# Main.net
KiCad netlist of a schematic drawn in Altium Designer
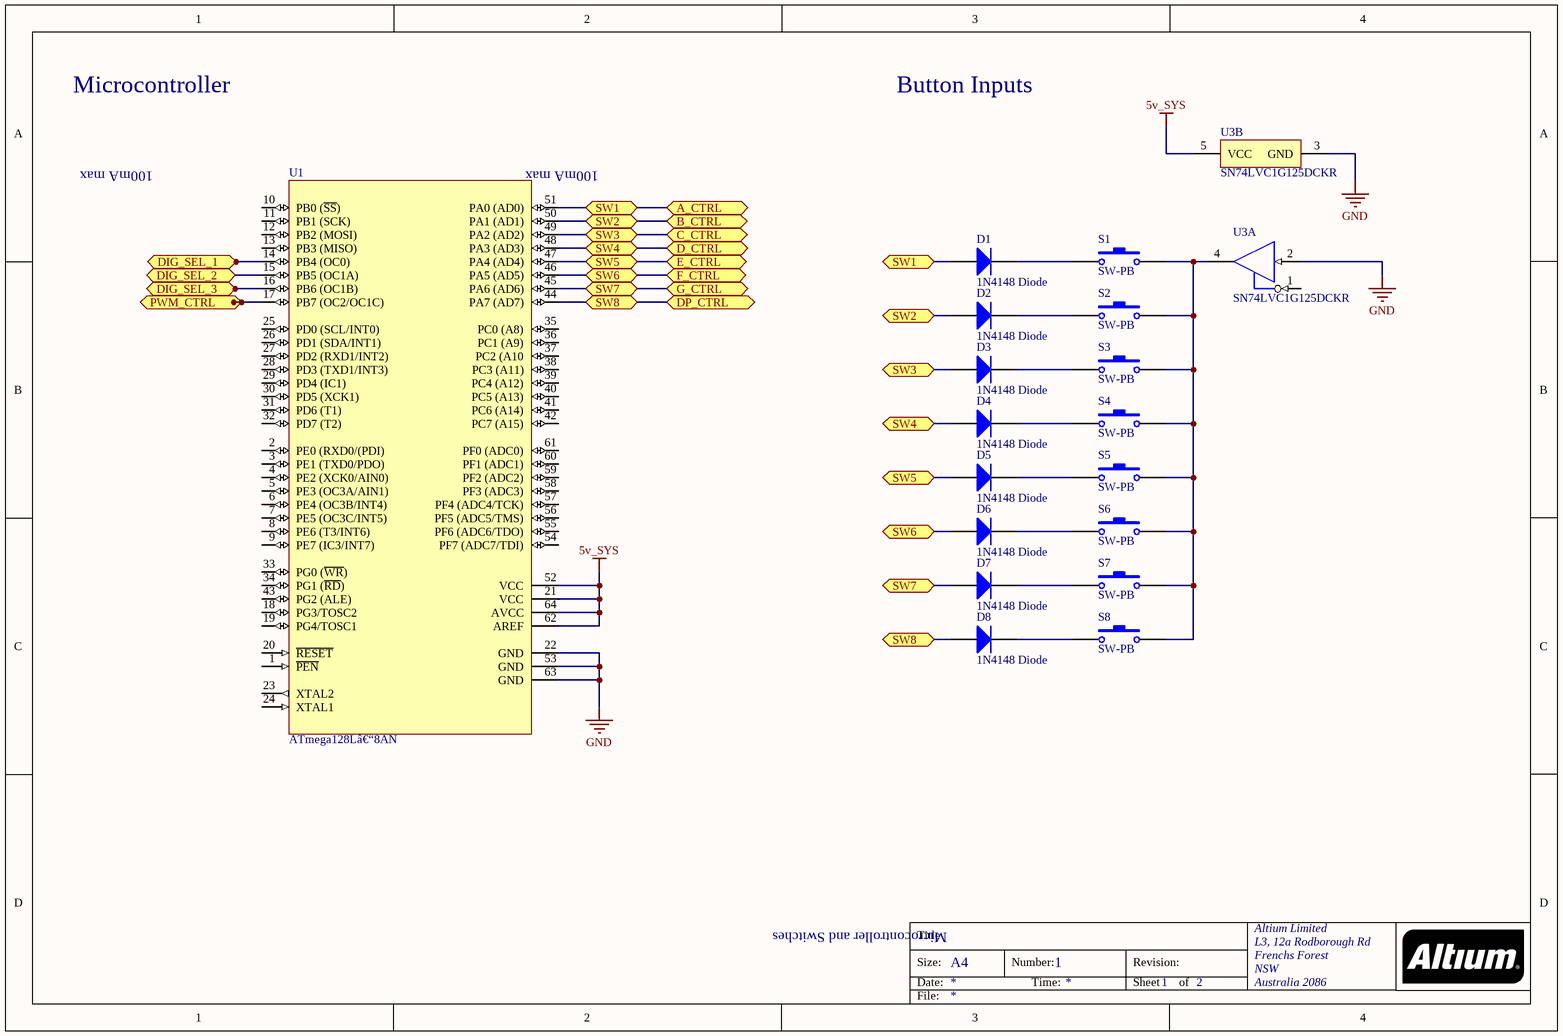
[diagram p0: Main.SchDoc]

(export (version "E")
  (design (tool "Eeschema 10.0.6"))
  (components
    (comp (ref "D1")
      (value "1N4148 Diode")
      (footprint "S01575 Diode")
      (description "Diode")
      (libsource (lib "lab2") (part "Diode"))
    )
    (comp (ref "D2")
      (value "1N4148 Diode")
      (footprint "S01575 Diode")
      (description "Diode")
      (libsource (lib "lab2") (part "Diode"))
    )
    (comp (ref "D3")
      (value "1N4148 Diode")
      (footprint "S01575 Diode")
      (description "Diode")
      (libsource (lib "lab2") (part "Diode"))
    )
    (comp (ref "D4")
      (value "1N4148 Diode")
      (footprint "S01575 Diode")
      (description "Diode")
      (libsource (lib "lab2") (part "Diode"))
    )
    (comp (ref "D5")
      (value "1N4148 Diode")
      (footprint "S01575 Diode")
      (description "Diode")
      (libsource (lib "lab2") (part "Diode"))
    )
    (comp (ref "D6")
      (value "1N4148 Diode")
      (footprint "S01575 Diode")
      (description "Diode")
      (libsource (lib "lab2") (part "Diode"))
    )
    (comp (ref "D7")
      (value "1N4148 Diode")
      (footprint "S01575 Diode")
      (description "Diode")
      (libsource (lib "lab2") (part "Diode"))
    )
    (comp (ref "D8")
      (value "1N4148 Diode")
      (footprint "S01575 Diode")
      (description "Diode")
      (libsource (lib "lab2") (part "Diode"))
    )
    (comp (ref "S1")
      (value "SW-PB")
      (footprint "SW-PB")
      (description "Switch")
      (libsource (lib "lab2") (part "SW-PB"))
    )
    (comp (ref "S2")
      (value "SW-PB")
      (footprint "SW-PB")
      (description "Switch")
      (libsource (lib "lab2") (part "SW-PB"))
    )
    (comp (ref "S3")
      (value "SW-PB")
      (footprint "SW-PB")
      (description "Switch")
      (libsource (lib "lab2") (part "SW-PB"))
    )
    (comp (ref "S4")
      (value "SW-PB")
      (footprint "SW-PB")
      (description "Switch")
      (libsource (lib "lab2") (part "SW-PB"))
    )
    (comp (ref "S5")
      (value "SW-PB")
      (footprint "SW-PB")
      (description "Switch")
      (libsource (lib "lab2") (part "SW-PB"))
    )
    (comp (ref "S6")
      (value "SW-PB")
      (footprint "SW-PB")
      (description "Switch")
      (libsource (lib "lab2") (part "SW-PB"))
    )
    (comp (ref "S7")
      (value "SW-PB")
      (footprint "SW-PB")
      (description "Switch")
      (libsource (lib "lab2") (part "SW-PB"))
    )
    (comp (ref "S8")
      (value "SW-PB")
      (footprint "SW-PB")
      (description "Switch")
      (libsource (lib "lab2") (part "SW-PB"))
    )
    (comp (ref "U1")
      (value "ATmega128Lâ€“8AN")
      (footprint "64A_L")
      (libsource (lib "Altium Content Vault") (part "MC-8B-AT64-SQ64"))
    )
    (comp (ref "U3")
      (value "SN74LVC1G125DCKR")
      (footprint "DCK0005A_N")
      (description "Single Bus Buffer Gate With 3-State Outputs, DCK0005A, LARGE T&R")
      (fields
        (field (name "GENERIC PART NUMBER") "SN74LVC1G125")
        (field (name "MANUFACTURER") "Texas Instruments")
      )
      (libsource (lib "") (part "TI-SN74AXXXX1X125-5_1"))
    )
  )
  (nets
    (net (code "1") (name "/A_CTRL") (class "Default")
      (node (ref "D1") (pin "3") (pinfunction "A_3") (pintype "passive"))
      (node (ref "U1") (pin "51") (pinfunction "PA0_(AD0)_51") (pintype "bidirectional"))
    )
    (net (code "2") (name "/B_CTRL") (class "Default")
      (node (ref "D2") (pin "3") (pinfunction "A_3") (pintype "passive"))
      (node (ref "U1") (pin "50") (pinfunction "PA1_(AD1)_50") (pintype "bidirectional"))
    )
    (net (code "3") (name "/C_CTRL") (class "Default")
      (node (ref "D3") (pin "3") (pinfunction "A_3") (pintype "passive"))
      (node (ref "U1") (pin "49") (pinfunction "PA2_(AD2)_49") (pintype "bidirectional"))
    )
    (net (code "4") (name "/DIG_SEL_1") (class "Default")
      (node (ref "U1") (pin "14") (pinfunction "PB4_(OC0)_14") (pintype "bidirectional"))
    )
    (net (code "5") (name "/DIG_SEL_2") (class "Default")
      (node (ref "U1") (pin "15") (pinfunction "PB5_(OC1A)_15") (pintype "bidirectional"))
    )
    (net (code "6") (name "/DIG_SEL_3") (class "Default")
      (node (ref "U1") (pin "16") (pinfunction "PB6_(OC1B)_16") (pintype "bidirectional"))
    )
    (net (code "7") (name "/DP_CTRL") (class "Default")
      (node (ref "D8") (pin "3") (pinfunction "A_3") (pintype "passive"))
      (node (ref "U1") (pin "44") (pinfunction "PA7_(AD7)_44") (pintype "bidirectional"))
    )
    (net (code "8") (name "/D_CTRL") (class "Default")
      (node (ref "D4") (pin "3") (pinfunction "A_3") (pintype "passive"))
      (node (ref "U1") (pin "48") (pinfunction "PA3_(AD3)_48") (pintype "bidirectional"))
    )
    (net (code "9") (name "/E_CTRL") (class "Default")
      (node (ref "D5") (pin "3") (pinfunction "A_3") (pintype "passive"))
      (node (ref "U1") (pin "47") (pinfunction "PA4_(AD4)_47") (pintype "bidirectional"))
    )
    (net (code "10") (name "/F_CTRL") (class "Default")
      (node (ref "D6") (pin "3") (pinfunction "A_3") (pintype "passive"))
      (node (ref "U1") (pin "46") (pinfunction "PA5_(AD5)_46") (pintype "bidirectional"))
    )
    (net (code "11") (name "/G_CTRL") (class "Default")
      (node (ref "D7") (pin "3") (pinfunction "A_3") (pintype "passive"))
      (node (ref "U1") (pin "45") (pinfunction "PA6_(AD6)_45") (pintype "bidirectional"))
    )
    (net (code "12") (name "/PWM_CTRL") (class "Default")
      (node (ref "U1") (pin "17") (pinfunction "PB7_(OC2/OC1C)_17") (pintype "bidirectional"))
    )
    (net (code "13") (name "5v_SYS") (class "Default")
      (node (ref "U1") (pin "21") (pinfunction "VCC_21") (pintype "power_in"))
      (node (ref "U1") (pin "52") (pinfunction "VCC_52") (pintype "power_in"))
      (node (ref "U1") (pin "62") (pinfunction "AREF_62") (pintype "passive"))
      (node (ref "U1") (pin "64") (pinfunction "AVCC_64") (pintype "power_in"))
      (node (ref "U3") (pin "5") (pinfunction "VCC_5") (pintype "power_in"))
    )
    (net (code "14") (name "GND") (class "Default")
      (node (ref "U1") (pin "22") (pinfunction "GND_22") (pintype "power_in"))
      (node (ref "U1") (pin "53") (pinfunction "GND_53") (pintype "power_in"))
      (node (ref "U1") (pin "63") (pinfunction "GND_63") (pintype "power_in"))
      (node (ref "U3") (pin "2") (pinfunction "A_2") (pintype "input"))
      (node (ref "U3") (pin "3") (pinfunction "GND_3") (pintype "power_in"))
    )
    (net (code "15") (name "Net-(D1-K)") (class "Default")
      (node (ref "D1") (pin "1") (pinfunction "K_1") (pintype "passive"))
      (node (ref "S1") (pin "1") (pinfunction "1_1") (pintype "passive"))
    )
    (net (code "16") (name "Net-(D2-K)") (class "Default")
      (node (ref "D2") (pin "1") (pinfunction "K_1") (pintype "passive"))
      (node (ref "S2") (pin "1") (pinfunction "1_1") (pintype "passive"))
    )
    (net (code "17") (name "Net-(D3-K)") (class "Default")
      (node (ref "D3") (pin "1") (pinfunction "K_1") (pintype "passive"))
      (node (ref "S3") (pin "1") (pinfunction "1_1") (pintype "passive"))
    )
    (net (code "18") (name "Net-(D4-K)") (class "Default")
      (node (ref "D4") (pin "1") (pinfunction "K_1") (pintype "passive"))
      (node (ref "S4") (pin "1") (pinfunction "1_1") (pintype "passive"))
    )
    (net (code "19") (name "Net-(D5-K)") (class "Default")
      (node (ref "D5") (pin "1") (pinfunction "K_1") (pintype "passive"))
      (node (ref "S5") (pin "1") (pinfunction "1_1") (pintype "passive"))
    )
    (net (code "20") (name "Net-(D6-K)") (class "Default")
      (node (ref "D6") (pin "1") (pinfunction "K_1") (pintype "passive"))
      (node (ref "S6") (pin "1") (pinfunction "1_1") (pintype "passive"))
    )
    (net (code "21") (name "Net-(D7-K)") (class "Default")
      (node (ref "D7") (pin "1") (pinfunction "K_1") (pintype "passive"))
      (node (ref "S7") (pin "1") (pinfunction "1_1") (pintype "passive"))
    )
    (net (code "22") (name "Net-(D8-K)") (class "Default")
      (node (ref "D8") (pin "1") (pinfunction "K_1") (pintype "passive"))
      (node (ref "S8") (pin "1") (pinfunction "1_1") (pintype "passive"))
    )
    (net (code "23") (name "Net-(U3A-Y)") (class "Default")
      (node (ref "S1") (pin "2") (pinfunction "2_2") (pintype "passive"))
      (node (ref "S2") (pin "2") (pinfunction "2_2") (pintype "passive"))
      (node (ref "S3") (pin "2") (pinfunction "2_2") (pintype "passive"))
      (node (ref "S4") (pin "2") (pinfunction "2_2") (pintype "passive"))
      (node (ref "S5") (pin "2") (pinfunction "2_2") (pintype "passive"))
      (node (ref "S6") (pin "2") (pinfunction "2_2") (pintype "passive"))
      (node (ref "S7") (pin "2") (pinfunction "2_2") (pintype "passive"))
      (node (ref "S8") (pin "2") (pinfunction "2_2") (pintype "passive"))
      (node (ref "U3") (pin "4") (pinfunction "Y_4") (pintype "tri_state"))
    )
    (net (code "24") (name "unconnected-(U1-PB0_(~{SS})-Pad10)") (class "Default")
      (node (ref "U1") (pin "10") (pinfunction "PB0_(~{SS})_10") (pintype "bidirectional"))
    )
    (net (code "25") (name "unconnected-(U1-PB1_(SCK)-Pad11)") (class "Default")
      (node (ref "U1") (pin "11") (pinfunction "PB1_(SCK)_11") (pintype "bidirectional"))
    )
    (net (code "26") (name "unconnected-(U1-PB2_(MOSI)-Pad12)") (class "Default")
      (node (ref "U1") (pin "12") (pinfunction "PB2_(MOSI)_12") (pintype "bidirectional"))
    )
    (net (code "27") (name "unconnected-(U1-PB3_(MISO)-Pad13)") (class "Default")
      (node (ref "U1") (pin "13") (pinfunction "PB3_(MISO)_13") (pintype "bidirectional"))
    )
    (net (code "28") (name "unconnected-(U1-PC0_(A8)-Pad35)") (class "Default")
      (node (ref "U1") (pin "35") (pinfunction "PC0_(A8)_35") (pintype "bidirectional"))
    )
    (net (code "29") (name "unconnected-(U1-PC1_(A9)-Pad36)") (class "Default")
      (node (ref "U1") (pin "36") (pinfunction "PC1_(A9)_36") (pintype "bidirectional"))
    )
    (net (code "30") (name "unconnected-(U1-PC2_(A10-Pad37)") (class "Default")
      (node (ref "U1") (pin "37") (pinfunction "PC2_(A10_37") (pintype "bidirectional"))
    )
    (net (code "31") (name "unconnected-(U1-PC3_(A11)-Pad38)") (class "Default")
      (node (ref "U1") (pin "38") (pinfunction "PC3_(A11)_38") (pintype "bidirectional"))
    )
    (net (code "32") (name "unconnected-(U1-PC4_(A12)-Pad39)") (class "Default")
      (node (ref "U1") (pin "39") (pinfunction "PC4_(A12)_39") (pintype "bidirectional"))
    )
    (net (code "33") (name "unconnected-(U1-PC5_(A13)-Pad40)") (class "Default")
      (node (ref "U1") (pin "40") (pinfunction "PC5_(A13)_40") (pintype "bidirectional"))
    )
    (net (code "34") (name "unconnected-(U1-PC6_(A14)-Pad41)") (class "Default")
      (node (ref "U1") (pin "41") (pinfunction "PC6_(A14)_41") (pintype "bidirectional"))
    )
    (net (code "35") (name "unconnected-(U1-PC7_(A15)-Pad42)") (class "Default")
      (node (ref "U1") (pin "42") (pinfunction "PC7_(A15)_42") (pintype "bidirectional"))
    )
    (net (code "36") (name "unconnected-(U1-PD0_(SCL{slash}INT0)-Pad25)") (class "Default")
      (node (ref "U1") (pin "25") (pinfunction "PD0_(SCL/INT0)_25") (pintype "bidirectional"))
    )
    (net (code "37") (name "unconnected-(U1-PD1_(SDA{slash}INT1)-Pad26)") (class "Default")
      (node (ref "U1") (pin "26") (pinfunction "PD1_(SDA/INT1)_26") (pintype "bidirectional"))
    )
    (net (code "38") (name "unconnected-(U1-PD2_(RXD1{slash}INT2)-Pad27)") (class "Default")
      (node (ref "U1") (pin "27") (pinfunction "PD2_(RXD1/INT2)_27") (pintype "bidirectional"))
    )
    (net (code "39") (name "unconnected-(U1-PD3_(TXD1{slash}INT3)-Pad28)") (class "Default")
      (node (ref "U1") (pin "28") (pinfunction "PD3_(TXD1/INT3)_28") (pintype "bidirectional"))
    )
    (net (code "40") (name "unconnected-(U1-PD4_(IC1)-Pad29)") (class "Default")
      (node (ref "U1") (pin "29") (pinfunction "PD4_(IC1)_29") (pintype "bidirectional"))
    )
    (net (code "41") (name "unconnected-(U1-PD5_(XCK1)-Pad30)") (class "Default")
      (node (ref "U1") (pin "30") (pinfunction "PD5_(XCK1)_30") (pintype "bidirectional"))
    )
    (net (code "42") (name "unconnected-(U1-PD6_(T1)-Pad31)") (class "Default")
      (node (ref "U1") (pin "31") (pinfunction "PD6_(T1)_31") (pintype "bidirectional"))
    )
    (net (code "43") (name "unconnected-(U1-PD7_(T2)-Pad32)") (class "Default")
      (node (ref "U1") (pin "32") (pinfunction "PD7_(T2)_32") (pintype "bidirectional"))
    )
    (net (code "44") (name "unconnected-(U1-PE0_(RXD0{slash}(PDI)-Pad2)") (class "Default")
      (node (ref "U1") (pin "2") (pinfunction "PE0_(RXD0/(PDI)_2") (pintype "bidirectional"))
    )
    (net (code "45") (name "unconnected-(U1-PE1_(TXD0{slash}PDO)-Pad3)") (class "Default")
      (node (ref "U1") (pin "3") (pinfunction "PE1_(TXD0/PDO)_3") (pintype "bidirectional"))
    )
    (net (code "46") (name "unconnected-(U1-PE2_(XCK0{slash}AIN0)-Pad4)") (class "Default")
      (node (ref "U1") (pin "4") (pinfunction "PE2_(XCK0/AIN0)_4") (pintype "bidirectional"))
    )
    (net (code "47") (name "unconnected-(U1-PE3_(OC3A{slash}AIN1)-Pad5)") (class "Default")
      (node (ref "U1") (pin "5") (pinfunction "PE3_(OC3A/AIN1)_5") (pintype "bidirectional"))
    )
    (net (code "48") (name "unconnected-(U1-PE4_(OC3B{slash}INT4)-Pad6)") (class "Default")
      (node (ref "U1") (pin "6") (pinfunction "PE4_(OC3B/INT4)_6") (pintype "bidirectional"))
    )
    (net (code "49") (name "unconnected-(U1-PE5_(OC3C{slash}INT5)-Pad7)") (class "Default")
      (node (ref "U1") (pin "7") (pinfunction "PE5_(OC3C/INT5)_7") (pintype "bidirectional"))
    )
    (net (code "50") (name "unconnected-(U1-PE6_(T3{slash}INT6)-Pad8)") (class "Default")
      (node (ref "U1") (pin "8") (pinfunction "PE6_(T3/INT6)_8") (pintype "bidirectional"))
    )
    (net (code "51") (name "unconnected-(U1-PE7_(IC3{slash}INT7)-Pad9)") (class "Default")
      (node (ref "U1") (pin "9") (pinfunction "PE7_(IC3/INT7)_9") (pintype "bidirectional"))
    )
    (net (code "52") (name "unconnected-(U1-PF0_(ADC0)-Pad61)") (class "Default")
      (node (ref "U1") (pin "61") (pinfunction "PF0_(ADC0)_61") (pintype "bidirectional"))
    )
    (net (code "53") (name "unconnected-(U1-PF1_(ADC1)-Pad60)") (class "Default")
      (node (ref "U1") (pin "60") (pinfunction "PF1_(ADC1)_60") (pintype "bidirectional"))
    )
    (net (code "54") (name "unconnected-(U1-PF2_(ADC2)-Pad59)") (class "Default")
      (node (ref "U1") (pin "59") (pinfunction "PF2_(ADC2)_59") (pintype "bidirectional"))
    )
    (net (code "55") (name "unconnected-(U1-PF3_(ADC3)-Pad58)") (class "Default")
      (node (ref "U1") (pin "58") (pinfunction "PF3_(ADC3)_58") (pintype "bidirectional"))
    )
    (net (code "56") (name "unconnected-(U1-PF4_(ADC4{slash}TCK)-Pad57)") (class "Default")
      (node (ref "U1") (pin "57") (pinfunction "PF4_(ADC4/TCK)_57") (pintype "bidirectional"))
    )
    (net (code "57") (name "unconnected-(U1-PF5_(ADC5{slash}TMS)-Pad56)") (class "Default")
      (node (ref "U1") (pin "56") (pinfunction "PF5_(ADC5/TMS)_56") (pintype "bidirectional"))
    )
    (net (code "58") (name "unconnected-(U1-PF6_(ADC6{slash}TDO)-Pad55)") (class "Default")
      (node (ref "U1") (pin "55") (pinfunction "PF6_(ADC6/TDO)_55") (pintype "bidirectional"))
    )
    (net (code "59") (name "unconnected-(U1-PF7_(ADC7{slash}TDI)-Pad54)") (class "Default")
      (node (ref "U1") (pin "54") (pinfunction "PF7_(ADC7/TDI)_54") (pintype "bidirectional"))
    )
    (net (code "60") (name "unconnected-(U1-PG0_(~{WR})-Pad33)") (class "Default")
      (node (ref "U1") (pin "33") (pinfunction "PG0_(~{WR})_33") (pintype "bidirectional"))
    )
    (net (code "61") (name "unconnected-(U1-PG1_(~{RD})-Pad34)") (class "Default")
      (node (ref "U1") (pin "34") (pinfunction "PG1_(~{RD})_34") (pintype "bidirectional"))
    )
    (net (code "62") (name "unconnected-(U1-PG2_(ALE)-Pad43)") (class "Default")
      (node (ref "U1") (pin "43") (pinfunction "PG2_(ALE)_43") (pintype "bidirectional"))
    )
    (net (code "63") (name "unconnected-(U1-PG3{slash}TOSC2-Pad18)") (class "Default")
      (node (ref "U1") (pin "18") (pinfunction "PG3/TOSC2_18") (pintype "bidirectional"))
    )
    (net (code "64") (name "unconnected-(U1-PG4{slash}TOSC1-Pad19)") (class "Default")
      (node (ref "U1") (pin "19") (pinfunction "PG4/TOSC1_19") (pintype "bidirectional"))
    )
    (net (code "65") (name "unconnected-(U1-XTAL1-Pad24)") (class "Default")
      (node (ref "U1") (pin "24") (pinfunction "XTAL1_24") (pintype "input"))
    )
    (net (code "66") (name "unconnected-(U1-XTAL2-Pad23)") (class "Default")
      (node (ref "U1") (pin "23") (pinfunction "XTAL2_23") (pintype "output"))
    )
    (net (code "67") (name "unconnected-(U1-~{PEN}-Pad1)") (class "Default")
      (node (ref "U1") (pin "1") (pinfunction "~{PEN}_1") (pintype "input"))
    )
    (net (code "68") (name "unconnected-(U1-~{RESET}-Pad20)") (class "Default")
      (node (ref "U1") (pin "20") (pinfunction "~{RESET}_20") (pintype "input"))
    )
    (net (code "69") (name "unconnected-(U3A-~{OE}-Pad1)") (class "Default")
      (node (ref "U3") (pin "1") (pinfunction "~{OE}_1") (pintype "input"))
    )
  )
)
